# motor.net
KiCad netlist of a schematic drawn in Altium Designer
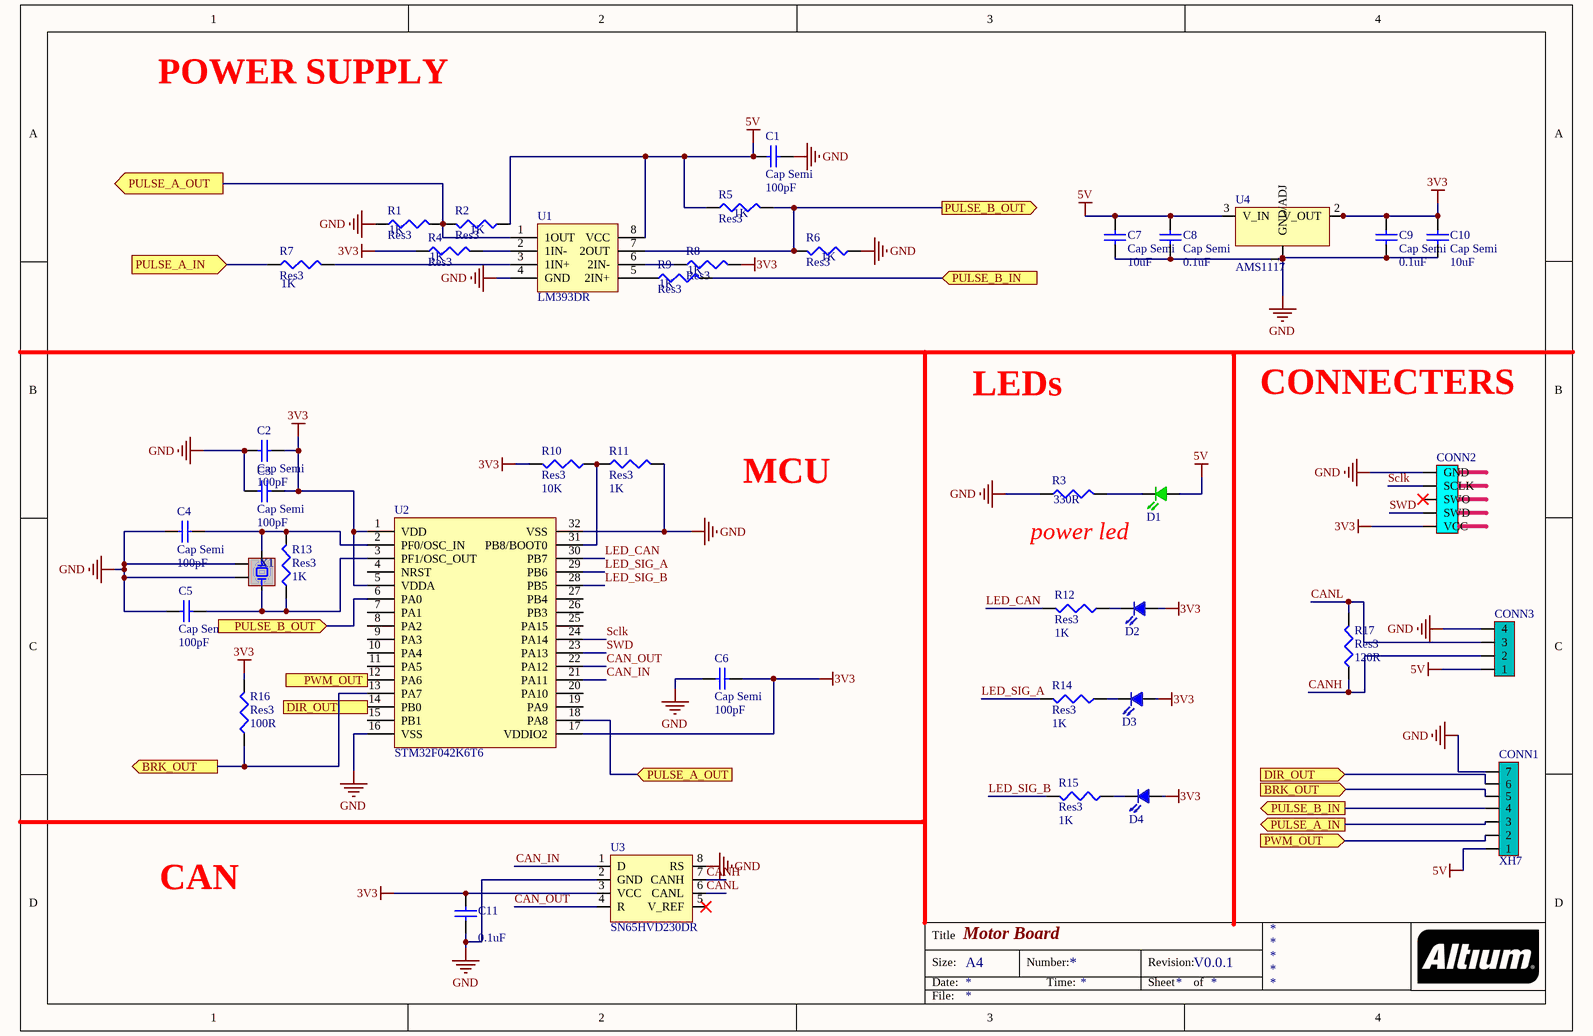
[diagram p0: motor.SchDoc]

(export (version "E")
  (design (tool "Eeschema 10.0.6"))
  (components
    (comp (ref "C1")
      (value "Cap Semi")
      (footprint "1608[0603]")
      (description "Capacitor (Semiconductor SIM Model)")
      (fields (field (name "ALTIUM_VALUE") "100pF") (field (name "PUBLISHER") "Altium Limited"))
      (libsource (lib "Miscellaneous Devices") (part "Cap Semi"))
    )
    (comp (ref "C2")
      (value "Cap Semi")
      (footprint "1608[0603]")
      (description "Capacitor (Semiconductor SIM Model)")
      (fields (field (name "ALTIUM_VALUE") "100pF") (field (name "PUBLISHER") "Altium Limited"))
      (libsource (lib "Miscellaneous Devices") (part "Cap Semi"))
    )
    (comp (ref "C3")
      (value "Cap Semi")
      (footprint "1608[0603]")
      (description "Capacitor (Semiconductor SIM Model)")
      (fields (field (name "ALTIUM_VALUE") "100pF") (field (name "PUBLISHER") "Altium Limited"))
      (libsource (lib "Miscellaneous Devices") (part "Cap Semi"))
    )
    (comp (ref "C4")
      (value "Cap Semi")
      (footprint "1608[0603]")
      (description "Capacitor (Semiconductor SIM Model)")
      (fields (field (name "ALTIUM_VALUE") "100pF") (field (name "PUBLISHER") "Altium Limited"))
      (libsource (lib "Miscellaneous Devices") (part "Cap Semi"))
    )
    (comp (ref "C5")
      (value "Cap Semi")
      (footprint "1608[0603]")
      (description "Capacitor (Semiconductor SIM Model)")
      (fields (field (name "ALTIUM_VALUE") "100pF") (field (name "PUBLISHER") "Altium Limited"))
      (libsource (lib "Miscellaneous Devices") (part "Cap Semi"))
    )
    (comp (ref "C6")
      (value "Cap Semi")
      (footprint "1608[0603]")
      (description "Capacitor (Semiconductor SIM Model)")
      (fields (field (name "ALTIUM_VALUE") "100pF") (field (name "PUBLISHER") "Altium Limited"))
      (libsource (lib "Miscellaneous Devices") (part "Cap Semi"))
    )
    (comp (ref "C7")
      (value "Cap Semi")
      (footprint "1608[0603]")
      (description "Capacitor (Semiconductor SIM Model)")
      (fields (field (name "ALTIUM_VALUE") "10uF") (field (name "PUBLISHER") "Altium Limited"))
      (libsource (lib "Miscellaneous Devices") (part "Cap Semi"))
    )
    (comp (ref "C8")
      (value "Cap Semi")
      (footprint "1608[0603]")
      (description "Capacitor (Semiconductor SIM Model)")
      (fields (field (name "ALTIUM_VALUE") "0.1uF") (field (name "PUBLISHER") "Altium Limited"))
      (libsource (lib "Miscellaneous Devices") (part "Cap Semi"))
    )
    (comp (ref "C9")
      (value "Cap Semi")
      (footprint "1608[0603]")
      (description "Capacitor (Semiconductor SIM Model)")
      (fields (field (name "ALTIUM_VALUE") "0.1uF") (field (name "PUBLISHER") "Altium Limited"))
      (libsource (lib "Miscellaneous Devices") (part "Cap Semi"))
    )
    (comp (ref "C10")
      (value "Cap Semi")
      (footprint "1608[0603]")
      (description "Capacitor (Semiconductor SIM Model)")
      (fields (field (name "ALTIUM_VALUE") "10uF") (field (name "PUBLISHER") "Altium Limited"))
      (libsource (lib "Miscellaneous Devices") (part "Cap Semi"))
    )
    (comp (ref "C11")
      (value "0.1uF")
      (footprint "1608[0603]")
      (description "Capacitor (Semiconductor SIM Model)")
      (fields (field (name "Comment") "Cap Semi") (field (name "PUBLISHER") "Altium Limited"))
      (libsource (lib "Miscellaneous Devices") (part "Cap Semi"))
    )
    (comp (ref "CONN1")
      (value "XH7")
      (footprint "XH2.54-LI-7P")
      (description "JST-SH 5-pin Side Entry Socket")
      (fields (field (name "MANUFACTURER") "Generic Components"))
      (libsource (lib "motor") (part "XH7"))
    )
    (comp (ref "CONN2") (value "~") (footprint "HDR1X5") (libsource (lib "motor") (part "Hdr 5 Pin 0.1")))
    (comp (ref "CONN3")
      (value "~")
      (footprint "XH2.54-LS-4P")
      (description "JST-SH 4-pin Side Entry Socket")
      (fields (field (name "MANUFACTURER") "Generic Components"))
      (libsource (lib "motor") (part "JST-4"))
    )
    (comp (ref "D1")
      (value "Green")
      (footprint "LED603N")
      (description "Green 603 LED")
      (libsource (lib "motor") (part "LED 603 Gr"))
    )
    (comp (ref "D2")
      (value "Blue")
      (footprint "LED603N")
      (description "Blue 603 LED")
      (libsource (lib "motor") (part "LED 603 Bl"))
    )
    (comp (ref "D3")
      (value "Blue")
      (footprint "LED603N")
      (description "Blue 603 LED")
      (libsource (lib "motor") (part "LED 603 Bl"))
    )
    (comp (ref "D4")
      (value "Blue")
      (footprint "LED603N")
      (description "Blue 603 LED")
      (libsource (lib "motor") (part "LED 603 Bl"))
    )
    (comp (ref "R1")
      (value "Res3")
      (footprint "J1-0603")
      (description "Resistor")
      (fields (field (name "ALTIUM_VALUE") "1K") (field (name "PUBLISHER") "Altium Limited"))
      (libsource (lib "Miscellaneous Devices") (part "Res3"))
    )
    (comp (ref "R2")
      (value "Res3")
      (footprint "J1-0603")
      (description "Resistor")
      (fields (field (name "ALTIUM_VALUE") "1K") (field (name "PUBLISHER") "Altium Limited"))
      (libsource (lib "Miscellaneous Devices") (part "Res3"))
    )
    (comp (ref "R3")
      (value "330R")
      (footprint "J1-0603")
      (description "Resistor")
      (fields (field (name "Comment") "Res3") (field (name "PUBLISHER") "Altium Limited"))
      (libsource (lib "Miscellaneous Devices") (part "Res3"))
    )
    (comp (ref "R4")
      (value "Res3")
      (footprint "J1-0603")
      (description "Resistor")
      (fields (field (name "ALTIUM_VALUE") "1K") (field (name "PUBLISHER") "Altium Limited"))
      (libsource (lib "Miscellaneous Devices") (part "Res3"))
    )
    (comp (ref "R5")
      (value "Res3")
      (footprint "J1-0603")
      (description "Resistor")
      (fields (field (name "ALTIUM_VALUE") "1K") (field (name "PUBLISHER") "Altium Limited"))
      (libsource (lib "Miscellaneous Devices") (part "Res3"))
    )
    (comp (ref "R6")
      (value "Res3")
      (footprint "J1-0603")
      (description "Resistor")
      (fields (field (name "ALTIUM_VALUE") "1K") (field (name "PUBLISHER") "Altium Limited"))
      (libsource (lib "Miscellaneous Devices") (part "Res3"))
    )
    (comp (ref "R7")
      (value "Res3")
      (footprint "J1-0603")
      (description "Resistor")
      (fields (field (name "ALTIUM_VALUE") "1K") (field (name "PUBLISHER") "Altium Limited"))
      (libsource (lib "Miscellaneous Devices") (part "Res3"))
    )
    (comp (ref "R8")
      (value "Res3")
      (footprint "J1-0603")
      (description "Resistor")
      (fields (field (name "ALTIUM_VALUE") "1K") (field (name "PUBLISHER") "Altium Limited"))
      (libsource (lib "Miscellaneous Devices") (part "Res3"))
    )
    (comp (ref "R9")
      (value "Res3")
      (footprint "J1-0603")
      (description "Resistor")
      (fields (field (name "ALTIUM_VALUE") "1K") (field (name "PUBLISHER") "Altium Limited"))
      (libsource (lib "Miscellaneous Devices") (part "Res3"))
    )
    (comp (ref "R10")
      (value "Res3")
      (footprint "J1-0603")
      (description "Resistor")
      (fields (field (name "ALTIUM_VALUE") "10K") (field (name "PUBLISHER") "Altium Limited"))
      (libsource (lib "Miscellaneous Devices") (part "Res3"))
    )
    (comp (ref "R11")
      (value "Res3")
      (footprint "J1-0603")
      (description "Resistor")
      (fields (field (name "ALTIUM_VALUE") "1K") (field (name "PUBLISHER") "Altium Limited"))
      (libsource (lib "Miscellaneous Devices") (part "Res3"))
    )
    (comp (ref "R12")
      (value "Res3")
      (footprint "J1-0603")
      (description "Resistor")
      (fields (field (name "ALTIUM_VALUE") "1K") (field (name "PUBLISHER") "Altium Limited"))
      (libsource (lib "Miscellaneous Devices") (part "Res3"))
    )
    (comp (ref "R13")
      (value "Res3")
      (footprint "J1-0603")
      (description "Resistor")
      (fields (field (name "ALTIUM_VALUE") "1K") (field (name "PUBLISHER") "Altium Limited"))
      (libsource (lib "Miscellaneous Devices") (part "Res3"))
    )
    (comp (ref "R14")
      (value "Res3")
      (footprint "J1-0603")
      (description "Resistor")
      (fields (field (name "ALTIUM_VALUE") "1K") (field (name "PUBLISHER") "Altium Limited"))
      (libsource (lib "Miscellaneous Devices") (part "Res3"))
    )
    (comp (ref "R15")
      (value "Res3")
      (footprint "J1-0603")
      (description "Resistor")
      (fields (field (name "ALTIUM_VALUE") "1K") (field (name "PUBLISHER") "Altium Limited"))
      (libsource (lib "Miscellaneous Devices") (part "Res3"))
    )
    (comp (ref "R16")
      (value "Res3")
      (footprint "J1-0603")
      (description "Resistor")
      (fields (field (name "ALTIUM_VALUE") "100R") (field (name "PUBLISHER") "Altium Limited"))
      (libsource (lib "Miscellaneous Devices") (part "Res3"))
    )
    (comp (ref "R17")
      (value "Res3")
      (footprint "J1-0603")
      (description "Resistor")
      (fields (field (name "ALTIUM_VALUE") "120R") (field (name "PUBLISHER") "Altium Limited"))
      (libsource (lib "Miscellaneous Devices") (part "Res3"))
    )
    (comp (ref "U1") (value "LM393DR") (footprint "LM393DR") (libsource (lib "motor") (part "LM393DR")))
    (comp (ref "U2")
      (value "STM32F042K6T6")
      (footprint "STM32 32 PIN")
      (libsource (lib "motor") (part "STM32F042K6T6"))
    )
    (comp (ref "U3")
      (value "SN65HVD230DR")
      (footprint "SN65HVD230")
      (libsource (lib "motor") (part "SN65HVD230DR"))
    )
    (comp (ref "U4")
      (value "AMS1117")
      (footprint "SOT230P700X180-4N")
      (libsource (lib "motor") (part "AMS1117"))
    )
    (comp (ref "X1")
      (value "8MHz")
      (footprint "XTAL ACT530SMX-4 Series")
      (description "Surface Mount Quartz Crystal, Digikey 535-9720-1-ND")
      (libsource (lib "motor") (part "XTAL ACT530SMX-4"))
    )
  )
  (nets
    (net (code "1") (name "/BRK_OUT") (class "Default")
      (node (ref "CONN1") (pin "5") (pinfunction "5_5") (pintype "passive"))
      (node (ref "R16") (pin "1") (pinfunction "1_1") (pintype "passive"))
      (node (ref "U2") (pin "13") (pinfunction "PA7_13") (pintype "passive"))
    )
    (net (code "2") (name "/CANH") (class "Default")
      (node (ref "CONN3") (pin "2") (pinfunction "2_2") (pintype "passive"))
      (node (ref "R17") (pin "1") (pinfunction "1_1") (pintype "passive"))
      (node (ref "U3") (pin "7") (pinfunction "CANH_7") (pintype "passive"))
    )
    (net (code "3") (name "/CANL") (class "Default")
      (node (ref "CONN3") (pin "3") (pinfunction "3_3") (pintype "passive"))
      (node (ref "R17") (pin "2") (pinfunction "2_2") (pintype "passive"))
      (node (ref "U3") (pin "6") (pinfunction "CANL_6") (pintype "passive"))
    )
    (net (code "4") (name "/CAN_IN") (class "Default")
      (node (ref "U2") (pin "21") (pinfunction "PA11_21") (pintype "passive"))
      (node (ref "U3") (pin "1") (pinfunction "D_1") (pintype "passive"))
    )
    (net (code "5") (name "/CAN_OUT") (class "Default")
      (node (ref "U2") (pin "22") (pinfunction "PA12_22") (pintype "passive"))
      (node (ref "U3") (pin "4") (pinfunction "R_4") (pintype "passive"))
    )
    (net (code "6") (name "/DIR_OUT") (class "Default")
      (node (ref "CONN1") (pin "6") (pinfunction "6_6") (pintype "passive"))
      (node (ref "U2") (pin "14") (pinfunction "PB0_14") (pintype "passive"))
    )
    (net (code "7") (name "/LED_CAN") (class "Default")
      (node (ref "R12") (pin "2") (pinfunction "2_2") (pintype "passive"))
      (node (ref "U2") (pin "30") (pinfunction "PB7_30") (pintype "passive"))
    )
    (net (code "8") (name "/LED_SIG_A") (class "Default")
      (node (ref "R14") (pin "2") (pinfunction "2_2") (pintype "passive"))
      (node (ref "U2") (pin "29") (pinfunction "PB6_29") (pintype "passive"))
    )
    (net (code "9") (name "/LED_SIG_B") (class "Default")
      (node (ref "R15") (pin "2") (pinfunction "2_2") (pintype "passive"))
      (node (ref "U2") (pin "28") (pinfunction "PB5_28") (pintype "passive"))
    )
    (net (code "10") (name "/PULSE_A_IN") (class "Default")
      (node (ref "CONN1") (pin "3") (pinfunction "3_3") (pintype "passive"))
      (node (ref "R7") (pin "1") (pinfunction "1_1") (pintype "passive"))
    )
    (net (code "11") (name "/PULSE_A_OUT") (class "Default")
      (node (ref "R1") (pin "2") (pinfunction "2_2") (pintype "passive"))
      (node (ref "R2") (pin "2") (pinfunction "2_2") (pintype "passive"))
      (node (ref "U1") (pin "1") (pinfunction "1OUT_1") (pintype "passive"))
      (node (ref "U2") (pin "18") (pinfunction "PA8_18") (pintype "passive"))
    )
    (net (code "12") (name "/PULSE_B_IN") (class "Default")
      (node (ref "CONN1") (pin "4") (pinfunction "4_4") (pintype "passive"))
      (node (ref "R9") (pin "2") (pinfunction "2_2") (pintype "passive"))
    )
    (net (code "13") (name "/PULSE_B_OUT") (class "Default")
      (node (ref "R5") (pin "2") (pinfunction "2_2") (pintype "passive"))
      (node (ref "R6") (pin "2") (pinfunction "2_2") (pintype "passive"))
      (node (ref "U1") (pin "7") (pinfunction "2OUT_7") (pintype "passive"))
      (node (ref "U2") (pin "6") (pinfunction "PA0_6") (pintype "passive"))
    )
    (net (code "14") (name "/PWM_OUT") (class "Default")
      (node (ref "CONN1") (pin "2") (pinfunction "2_2") (pintype "passive"))
      (node (ref "U2") (pin "12") (pinfunction "PA6_12") (pintype "passive"))
    )
    (net (code "15") (name "/SWD") (class "Default")
      (node (ref "CONN2") (pin "2") (pinfunction "SWD_2") (pintype "passive"))
      (node (ref "U2") (pin "23") (pinfunction "PA13_23") (pintype "passive"))
    )
    (net (code "16") (name "/Sclk") (class "Default")
      (node (ref "CONN2") (pin "4") (pinfunction "SCLK_4") (pintype "passive"))
      (node (ref "U2") (pin "24") (pinfunction "PA14_24") (pintype "passive"))
    )
    (net (code "17") (name "3V3") (class "Default")
      (node (ref "C10") (pin "2") (pinfunction "2_2") (pintype "passive"))
      (node (ref "C11") (pin "2") (pinfunction "2_2") (pintype "passive"))
      (node (ref "C2") (pin "2") (pinfunction "2_2") (pintype "passive"))
      (node (ref "C3") (pin "2") (pinfunction "2_2") (pintype "passive"))
      (node (ref "C6") (pin "1") (pinfunction "1_1") (pintype "passive"))
      (node (ref "C9") (pin "2") (pinfunction "2_2") (pintype "passive"))
      (node (ref "CONN2") (pin "1") (pinfunction "VCC_1") (pintype "passive"))
      (node (ref "D2") (pin "2") (pinfunction "A_2") (pintype "passive"))
      (node (ref "D3") (pin "2") (pinfunction "A_2") (pintype "passive"))
      (node (ref "D4") (pin "2") (pinfunction "A_2") (pintype "passive"))
      (node (ref "R10") (pin "2") (pinfunction "2_2") (pintype "passive"))
      (node (ref "R16") (pin "2") (pinfunction "2_2") (pintype "passive"))
      (node (ref "R4") (pin "1") (pinfunction "1_1") (pintype "passive"))
      (node (ref "R8") (pin "2") (pinfunction "2_2") (pintype "passive"))
      (node (ref "U2") (pin "1") (pinfunction "VDD_1") (pintype "passive"))
      (node (ref "U2") (pin "17") (pinfunction "VDDIO2_17") (pintype "passive"))
      (node (ref "U2") (pin "5") (pinfunction "VDDA_5") (pintype "passive"))
      (node (ref "U3") (pin "3") (pinfunction "VCC_3") (pintype "passive"))
      (node (ref "U4") (pin "2") (pinfunction "V_OUT_2") (pintype "passive"))
    )
    (net (code "18") (name "5V") (class "Default")
      (node (ref "C1") (pin "1") (pinfunction "1_1") (pintype "passive"))
      (node (ref "C7") (pin "2") (pinfunction "2_2") (pintype "passive"))
      (node (ref "C8") (pin "2") (pinfunction "2_2") (pintype "passive"))
      (node (ref "CONN1") (pin "1") (pinfunction "1_1") (pintype "passive"))
      (node (ref "CONN3") (pin "1") (pinfunction "1_1") (pintype "passive"))
      (node (ref "D1") (pin "2") (pinfunction "A_2") (pintype "passive"))
      (node (ref "R2") (pin "1") (pinfunction "1_1") (pintype "passive"))
      (node (ref "R5") (pin "1") (pinfunction "1_1") (pintype "passive"))
      (node (ref "U1") (pin "8") (pinfunction "VCC_8") (pintype "passive"))
      (node (ref "U4") (pin "3") (pinfunction "V_IN_3") (pintype "passive"))
    )
    (net (code "19") (name "GND") (class "Default")
      (node (ref "C1") (pin "2") (pinfunction "2_2") (pintype "passive"))
      (node (ref "C10") (pin "1") (pinfunction "1_1") (pintype "passive"))
      (node (ref "C11") (pin "1") (pinfunction "1_1") (pintype "passive"))
      (node (ref "C2") (pin "1") (pinfunction "1_1") (pintype "passive"))
      (node (ref "C3") (pin "1") (pinfunction "1_1") (pintype "passive"))
      (node (ref "C4") (pin "1") (pinfunction "1_1") (pintype "passive"))
      (node (ref "C5") (pin "1") (pinfunction "1_1") (pintype "passive"))
      (node (ref "C6") (pin "2") (pinfunction "2_2") (pintype "passive"))
      (node (ref "C7") (pin "1") (pinfunction "1_1") (pintype "passive"))
      (node (ref "C8") (pin "1") (pinfunction "1_1") (pintype "passive"))
      (node (ref "C9") (pin "1") (pinfunction "1_1") (pintype "passive"))
      (node (ref "CONN1") (pin "7") (pinfunction "7_7") (pintype "passive"))
      (node (ref "CONN2") (pin "5") (pinfunction "GND_5") (pintype "passive"))
      (node (ref "CONN3") (pin "4") (pinfunction "4_4") (pintype "passive"))
      (node (ref "R1") (pin "1") (pinfunction "1_1") (pintype "passive"))
      (node (ref "R11") (pin "2") (pinfunction "2_2") (pintype "passive"))
      (node (ref "R3") (pin "1") (pinfunction "1_1") (pintype "passive"))
      (node (ref "R6") (pin "1") (pinfunction "1_1") (pintype "passive"))
      (node (ref "U1") (pin "4") (pinfunction "GND_4") (pintype "passive"))
      (node (ref "U2") (pin "16") (pinfunction "VSS_16") (pintype "passive"))
      (node (ref "U2") (pin "32") (pinfunction "VSS_32") (pintype "passive"))
      (node (ref "U3") (pin "2") (pinfunction "GND_2") (pintype "passive"))
      (node (ref "U3") (pin "8") (pinfunction "RS_8") (pintype "passive"))
      (node (ref "U4") (pin "1") (pinfunction "GND/ADJ_1") (pintype "passive"))
      (node (ref "X1") (pin "2") (pinfunction "2_2") (pintype "passive"))
      (node (ref "X1") (pin "4") (pinfunction "4_4") (pintype "passive"))
    )
    (net (code "20") (name "Net-(D1-K)") (class "Default")
      (node (ref "D1") (pin "1") (pinfunction "K_1") (pintype "passive"))
      (node (ref "R3") (pin "2") (pinfunction "2_2") (pintype "passive"))
    )
    (net (code "21") (name "Net-(D2-K)") (class "Default")
      (node (ref "D2") (pin "1") (pinfunction "K_1") (pintype "passive"))
      (node (ref "R12") (pin "1") (pinfunction "1_1") (pintype "passive"))
    )
    (net (code "22") (name "Net-(D3-K)") (class "Default")
      (node (ref "D3") (pin "1") (pinfunction "K_1") (pintype "passive"))
      (node (ref "R14") (pin "1") (pinfunction "1_1") (pintype "passive"))
    )
    (net (code "23") (name "Net-(D4-K)") (class "Default")
      (node (ref "D4") (pin "1") (pinfunction "K_1") (pintype "passive"))
      (node (ref "R15") (pin "1") (pinfunction "1_1") (pintype "passive"))
    )
    (net (code "24") (name "Net-(U1-1IN+)") (class "Default")
      (node (ref "R7") (pin "2") (pinfunction "2_2") (pintype "passive"))
      (node (ref "U1") (pin "3") (pinfunction "1IN+_3") (pintype "passive"))
    )
    (net (code "25") (name "Net-(U1-1IN-)") (class "Default")
      (node (ref "R4") (pin "2") (pinfunction "2_2") (pintype "passive"))
      (node (ref "U1") (pin "2") (pinfunction "1IN-_2") (pintype "passive"))
    )
    (net (code "26") (name "Net-(U1-2IN+)") (class "Default")
      (node (ref "R9") (pin "1") (pinfunction "1_1") (pintype "passive"))
      (node (ref "U1") (pin "5") (pinfunction "2IN+_5") (pintype "passive"))
    )
    (net (code "27") (name "Net-(U1-2IN-)") (class "Default")
      (node (ref "R8") (pin "1") (pinfunction "1_1") (pintype "passive"))
      (node (ref "U1") (pin "6") (pinfunction "2IN-_6") (pintype "passive"))
    )
    (net (code "28") (name "Net-(U2-PB8{slash}BOOT0)") (class "Default")
      (node (ref "R10") (pin "1") (pinfunction "1_1") (pintype "passive"))
      (node (ref "R11") (pin "1") (pinfunction "1_1") (pintype "passive"))
      (node (ref "U2") (pin "31") (pinfunction "PB8/BOOT0_31") (pintype "passive"))
    )
    (net (code "29") (name "Net-(U2-PF0{slash}OSC_IN)") (class "Default")
      (node (ref "C4") (pin "2") (pinfunction "2_2") (pintype "passive"))
      (node (ref "R13") (pin "2") (pinfunction "2_2") (pintype "passive"))
      (node (ref "U2") (pin "2") (pinfunction "PF0/OSC_IN_2") (pintype "passive"))
      (node (ref "X1") (pin "3") (pinfunction "3_3") (pintype "passive"))
    )
    (net (code "30") (name "Net-(U2-PF1{slash}OSC_OUT)") (class "Default")
      (node (ref "C5") (pin "2") (pinfunction "2_2") (pintype "passive"))
      (node (ref "R13") (pin "1") (pinfunction "1_1") (pintype "passive"))
      (node (ref "U2") (pin "3") (pinfunction "PF1/OSC_OUT_3") (pintype "passive"))
      (node (ref "X1") (pin "1") (pinfunction "1_1") (pintype "passive"))
    )
    (net (code "31") (name "unconnected-(CONN2-SWO-Pad3)") (class "Default")
      (node (ref "CONN2") (pin "3") (pinfunction "SWO_3") (pintype "passive+no_connect"))
    )
    (net (code "32") (name "unconnected-(U2-NRST-Pad4)") (class "Default")
      (node (ref "U2") (pin "4") (pinfunction "NRST_4") (pintype "passive"))
    )
    (net (code "33") (name "unconnected-(U2-PA1-Pad7)") (class "Default")
      (node (ref "U2") (pin "7") (pinfunction "PA1_7") (pintype "passive"))
    )
    (net (code "34") (name "unconnected-(U2-PA2-Pad8)") (class "Default")
      (node (ref "U2") (pin "8") (pinfunction "PA2_8") (pintype "passive"))
    )
    (net (code "35") (name "unconnected-(U2-PA3-Pad9)") (class "Default")
      (node (ref "U2") (pin "9") (pinfunction "PA3_9") (pintype "passive"))
    )
    (net (code "36") (name "unconnected-(U2-PA4-Pad10)") (class "Default")
      (node (ref "U2") (pin "10") (pinfunction "PA4_10") (pintype "passive"))
    )
    (net (code "37") (name "unconnected-(U2-PA5-Pad11)") (class "Default")
      (node (ref "U2") (pin "11") (pinfunction "PA5_11") (pintype "passive"))
    )
    (net (code "38") (name "unconnected-(U2-PA9-Pad19)") (class "Default")
      (node (ref "U2") (pin "19") (pinfunction "PA9_19") (pintype "passive"))
    )
    (net (code "39") (name "unconnected-(U2-PA10-Pad20)") (class "Default")
      (node (ref "U2") (pin "20") (pinfunction "PA10_20") (pintype "passive"))
    )
    (net (code "40") (name "unconnected-(U2-PA15-Pad25)") (class "Default")
      (node (ref "U2") (pin "25") (pinfunction "PA15_25") (pintype "passive"))
    )
    (net (code "41") (name "unconnected-(U2-PB1-Pad15)") (class "Default")
      (node (ref "U2") (pin "15") (pinfunction "PB1_15") (pintype "passive"))
    )
    (net (code "42") (name "unconnected-(U2-PB3-Pad26)") (class "Default")
      (node (ref "U2") (pin "26") (pinfunction "PB3_26") (pintype "passive"))
    )
    (net (code "43") (name "unconnected-(U2-PB4-Pad27)") (class "Default")
      (node (ref "U2") (pin "27") (pinfunction "PB4_27") (pintype "passive"))
    )
    (net (code "44") (name "unconnected-(U3-V_REF-Pad5)") (class "Default")
      (node (ref "U3") (pin "5") (pinfunction "V_REF_5") (pintype "passive+no_connect"))
    )
  )
)
